# Power_Supply_Page_for_RK3399.net
KiCad netlist of a schematic drawn in Altium Designer
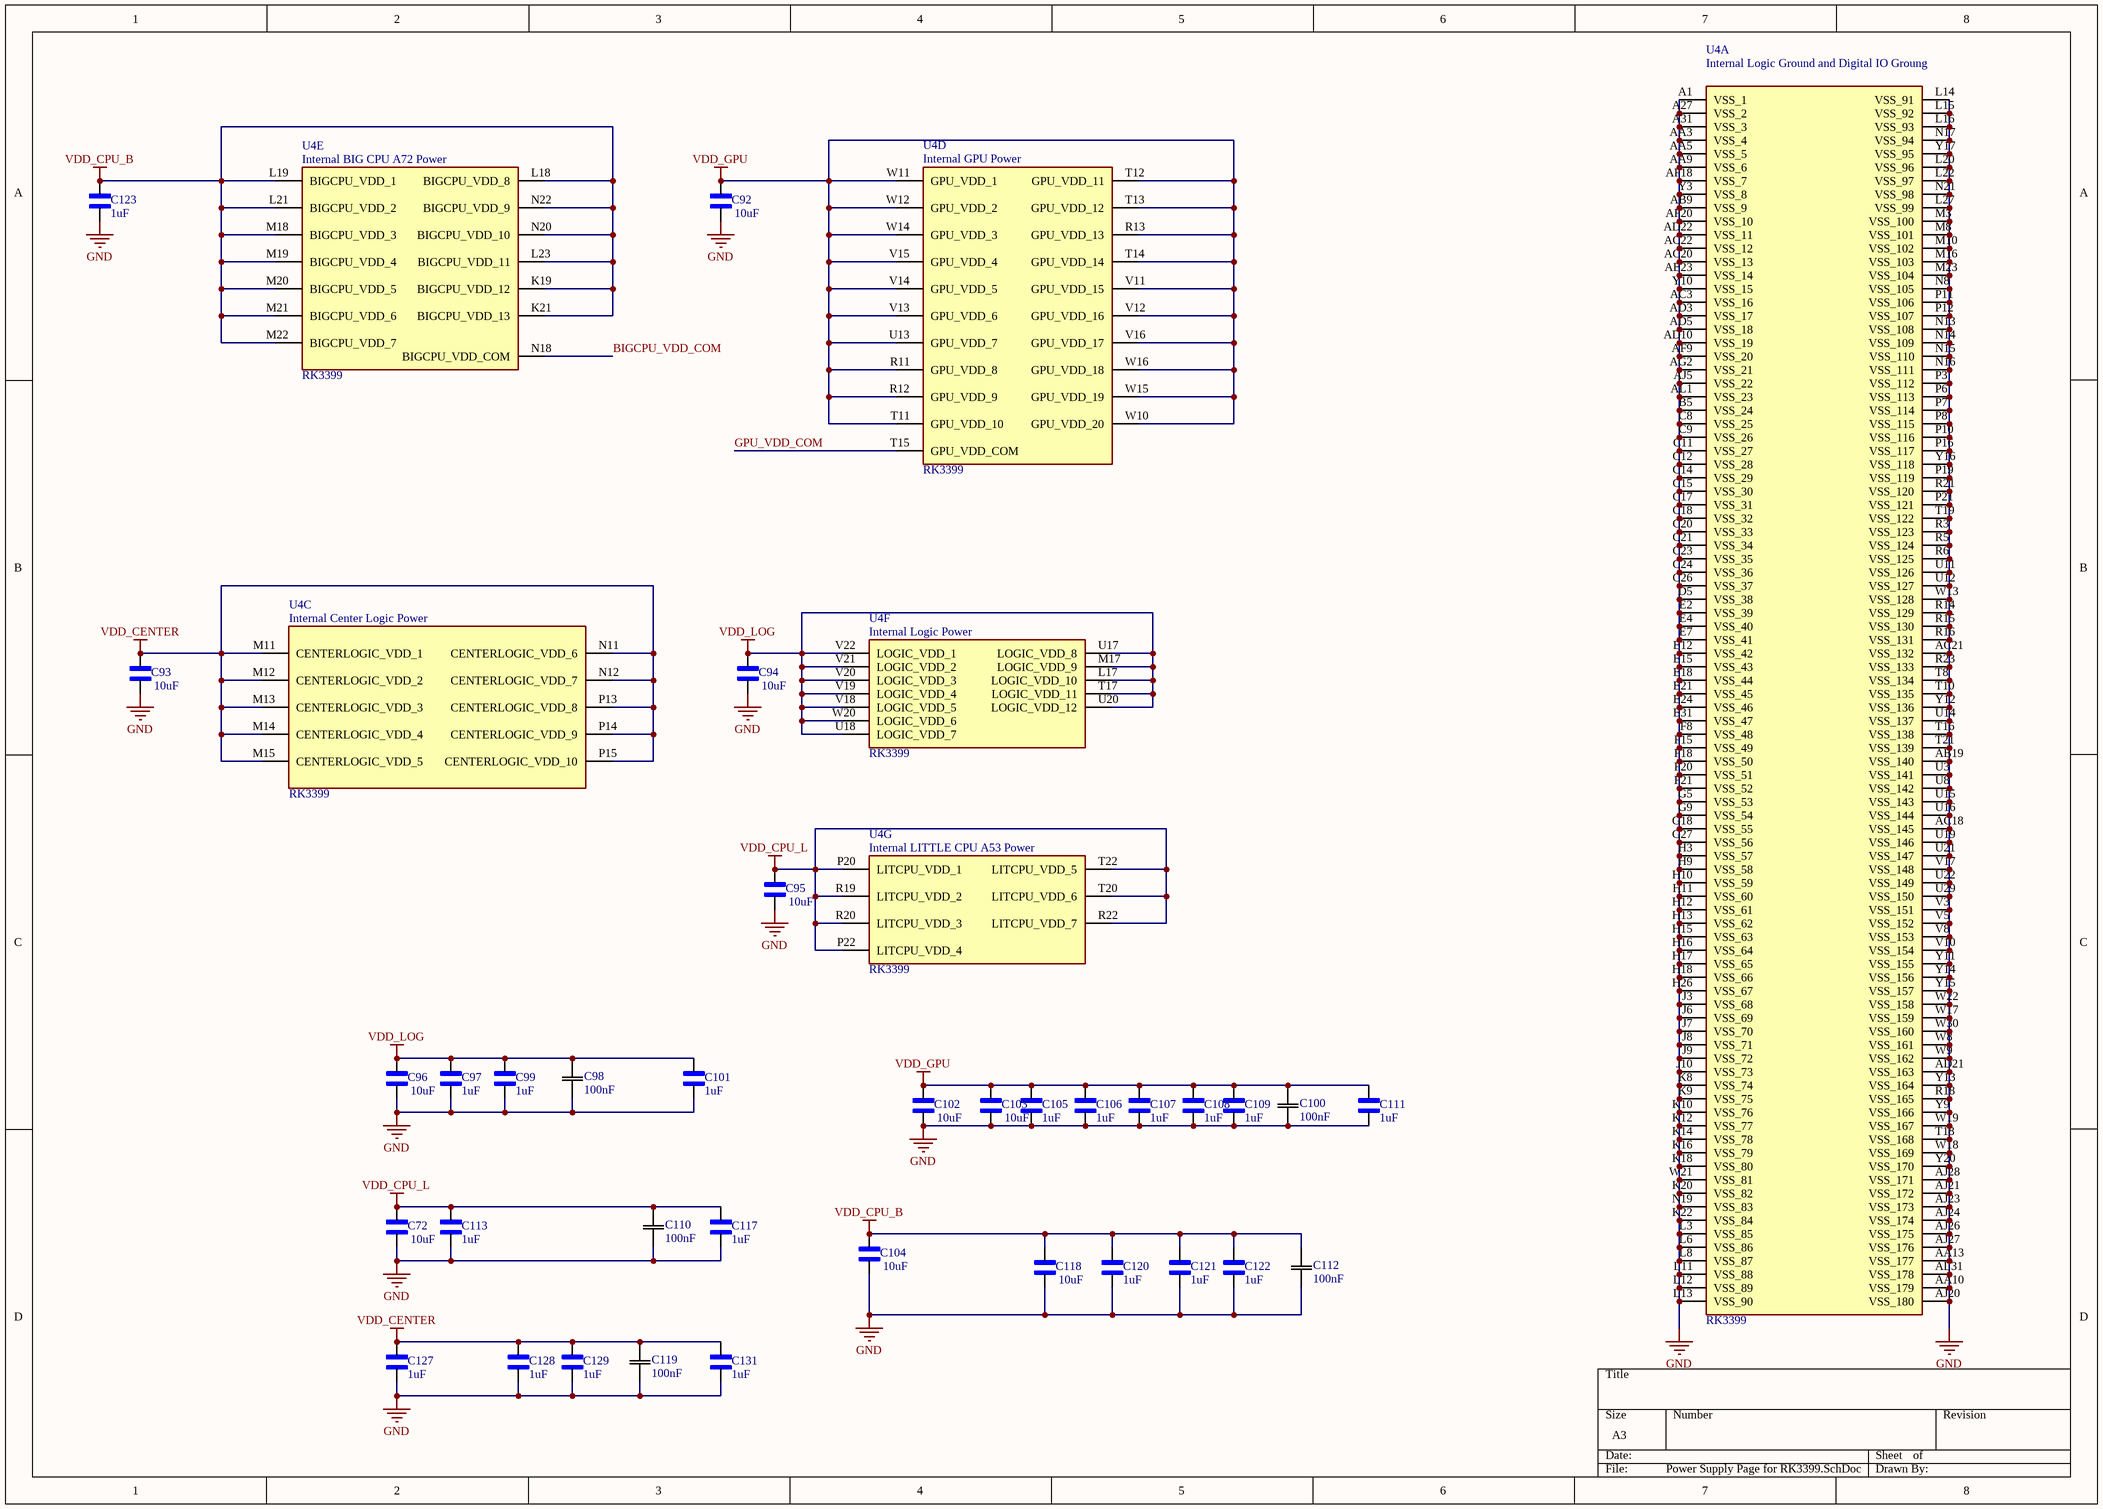
[diagram p0: Power Supply Page for RK3399.SchDoc]

(export (version "E")
  (design (tool "Eeschema 10.0.6"))
  (components
    (comp (ref "C72")
      (value "10uF")
      (footprint "CAPC1005X70N")
      (description "10 ÂµF Â±20% 6.3V Ceramic Capacitor X5R 0402 (1005 Metric)")
      (fields (field (name "MF") "Samsung") (field (name "MP") "CL05A106MQ5NUNC"))
      (libsource (lib "CL05A106MQ5NUNC") (part "CL05A106MQ5NUNC"))
    )
    (comp (ref "C92")
      (value "10uF")
      (footprint "CAPC1005X70N")
      (description "10 ÂµF Â±20% 6.3V Ceramic Capacitor X5R 0402 (1005 Metric)")
      (fields (field (name "MF") "Samsung") (field (name "MP") "CL05A106MQ5NUNC"))
      (libsource (lib "CL05A106MQ5NUNC") (part "CL05A106MQ5NUNC"))
    )
    (comp (ref "C93")
      (value "10uF")
      (footprint "CAPC1005X70N")
      (description "10 ÂµF Â±20% 6.3V Ceramic Capacitor X5R 0402 (1005 Metric)")
      (fields (field (name "MF") "Samsung") (field (name "MP") "CL05A106MQ5NUNC"))
      (libsource (lib "CL05A106MQ5NUNC") (part "CL05A106MQ5NUNC"))
    )
    (comp (ref "C94")
      (value "10uF")
      (footprint "CAPC1005X70N")
      (description "10 ÂµF Â±20% 6.3V Ceramic Capacitor X5R 0402 (1005 Metric)")
      (fields (field (name "MF") "Samsung") (field (name "MP") "CL05A106MQ5NUNC"))
      (libsource (lib "CL05A106MQ5NUNC") (part "CL05A106MQ5NUNC"))
    )
    (comp (ref "C95")
      (value "10uF")
      (footprint "CAPC1005X70N")
      (description "10 ÂµF Â±20% 6.3V Ceramic Capacitor X5R 0402 (1005 Metric)")
      (fields (field (name "MF") "Samsung") (field (name "MP") "CL05A106MQ5NUNC"))
      (libsource (lib "CL05A106MQ5NUNC") (part "CL05A106MQ5NUNC"))
    )
    (comp (ref "C96")
      (value "10uF")
      (footprint "CAPC1005X70N")
      (description "10 ÂµF Â±20% 6.3V Ceramic Capacitor X5R 0402 (1005 Metric)")
      (fields (field (name "MF") "Samsung") (field (name "MP") "CL05A106MQ5NUNC"))
      (libsource (lib "CL05A106MQ5NUNC") (part "CL05A106MQ5NUNC"))
    )
    (comp (ref "C97")
      (value "1uF")
      (footprint "CAPC1005X56N")
      (description "1 ÂµF Â±10% 10V Ceramic Capacitor X5R 0402 (1005 Metric)")
      (fields (field (name "MF") "AVX") (field (name "MP") "0402ZD105KAT4A"))
      (libsource (lib "0402ZD105KAT4A") (part "0402ZD105KAT4A"))
    )
    (comp (ref "C98")
      (value "100nF")
      (footprint "CAP_1005_TDK")
      (description "Description")
      (fields
        (field (name "MANUFACTURER_PART_NUMBER") "C1005X7R1H104M050BB")
        (field (name "COPYRIGHT") "Copyright (C) 2025 Ultra Librarian. All rights reserved.")
      )
      (libsource (lib "C1005X7R1H104M050BB") (part "C1005X7R1H104M050BB"))
    )
    (comp (ref "C99")
      (value "1uF")
      (footprint "CAPC1005X56N")
      (description "1 ÂµF Â±10% 10V Ceramic Capacitor X5R 0402 (1005 Metric)")
      (fields (field (name "MF") "AVX") (field (name "MP") "0402ZD105KAT4A"))
      (libsource (lib "0402ZD105KAT4A") (part "0402ZD105KAT4A"))
    )
    (comp (ref "C100")
      (value "100nF")
      (footprint "CAP_1005_TDK")
      (description "Description")
      (fields
        (field (name "MANUFACTURER_PART_NUMBER") "C1005X7R1H104M050BB")
        (field (name "COPYRIGHT") "Copyright (C) 2025 Ultra Librarian. All rights reserved.")
      )
      (libsource (lib "C1005X7R1H104M050BB") (part "C1005X7R1H104M050BB"))
    )
    (comp (ref "C101")
      (value "1uF")
      (footprint "CAPC1005X56N")
      (description "1 ÂµF Â±10% 10V Ceramic Capacitor X5R 0402 (1005 Metric)")
      (fields (field (name "MF") "AVX") (field (name "MP") "0402ZD105KAT4A"))
      (libsource (lib "0402ZD105KAT4A") (part "0402ZD105KAT4A"))
    )
    (comp (ref "C102")
      (value "10uF")
      (footprint "CAPC1005X70N")
      (description "10 ÂµF Â±20% 6.3V Ceramic Capacitor X5R 0402 (1005 Metric)")
      (fields (field (name "MF") "Samsung") (field (name "MP") "CL05A106MQ5NUNC"))
      (libsource (lib "CL05A106MQ5NUNC") (part "CL05A106MQ5NUNC"))
    )
    (comp (ref "C103")
      (value "10uF")
      (footprint "CAPC1005X70N")
      (description "10 ÂµF Â±20% 6.3V Ceramic Capacitor X5R 0402 (1005 Metric)")
      (fields (field (name "MF") "Samsung") (field (name "MP") "CL05A106MQ5NUNC"))
      (libsource (lib "CL05A106MQ5NUNC") (part "CL05A106MQ5NUNC"))
    )
    (comp (ref "C104")
      (value "10uF")
      (footprint "CAPC1005X70N")
      (description "10 ÂµF Â±20% 6.3V Ceramic Capacitor X5R 0402 (1005 Metric)")
      (fields (field (name "MF") "Samsung") (field (name "MP") "CL05A106MQ5NUNC"))
      (libsource (lib "CL05A106MQ5NUNC") (part "CL05A106MQ5NUNC"))
    )
    (comp (ref "C105")
      (value "1uF")
      (footprint "CAPC1005X56N")
      (description "1 ÂµF Â±10% 10V Ceramic Capacitor X5R 0402 (1005 Metric)")
      (fields (field (name "MF") "AVX") (field (name "MP") "0402ZD105KAT4A"))
      (libsource (lib "0402ZD105KAT4A") (part "0402ZD105KAT4A"))
    )
    (comp (ref "C106")
      (value "1uF")
      (footprint "CAPC1005X56N")
      (description "1 ÂµF Â±10% 10V Ceramic Capacitor X5R 0402 (1005 Metric)")
      (fields (field (name "MF") "AVX") (field (name "MP") "0402ZD105KAT4A"))
      (libsource (lib "0402ZD105KAT4A") (part "0402ZD105KAT4A"))
    )
    (comp (ref "C107")
      (value "1uF")
      (footprint "CAPC1005X56N")
      (description "1 ÂµF Â±10% 10V Ceramic Capacitor X5R 0402 (1005 Metric)")
      (fields (field (name "MF") "AVX") (field (name "MP") "0402ZD105KAT4A"))
      (libsource (lib "0402ZD105KAT4A") (part "0402ZD105KAT4A"))
    )
    (comp (ref "C108")
      (value "1uF")
      (footprint "CAPC1005X56N")
      (description "1 ÂµF Â±10% 10V Ceramic Capacitor X5R 0402 (1005 Metric)")
      (fields (field (name "MF") "AVX") (field (name "MP") "0402ZD105KAT4A"))
      (libsource (lib "0402ZD105KAT4A") (part "0402ZD105KAT4A"))
    )
    (comp (ref "C109")
      (value "1uF")
      (footprint "CAPC1005X56N")
      (description "1 ÂµF Â±10% 10V Ceramic Capacitor X5R 0402 (1005 Metric)")
      (fields (field (name "MF") "AVX") (field (name "MP") "0402ZD105KAT4A"))
      (libsource (lib "0402ZD105KAT4A") (part "0402ZD105KAT4A"))
    )
    (comp (ref "C110")
      (value "100nF")
      (footprint "CAP_1005_TDK")
      (description "Description")
      (fields
        (field (name "MANUFACTURER_PART_NUMBER") "C1005X7R1H104M050BB")
        (field (name "COPYRIGHT") "Copyright (C) 2025 Ultra Librarian. All rights reserved.")
      )
      (libsource (lib "C1005X7R1H104M050BB") (part "C1005X7R1H104M050BB"))
    )
    (comp (ref "C111")
      (value "1uF")
      (footprint "CAPC1005X56N")
      (description "1 ÂµF Â±10% 10V Ceramic Capacitor X5R 0402 (1005 Metric)")
      (fields (field (name "MF") "AVX") (field (name "MP") "0402ZD105KAT4A"))
      (libsource (lib "0402ZD105KAT4A") (part "0402ZD105KAT4A"))
    )
    (comp (ref "C112")
      (value "100nF")
      (footprint "CAP_1005_TDK")
      (description "Description")
      (fields
        (field (name "MANUFACTURER_PART_NUMBER") "C1005X7R1H104M050BB")
        (field (name "COPYRIGHT") "Copyright (C) 2025 Ultra Librarian. All rights reserved.")
      )
      (libsource (lib "C1005X7R1H104M050BB") (part "C1005X7R1H104M050BB"))
    )
    (comp (ref "C113")
      (value "1uF")
      (footprint "CAPC1005X56N")
      (description "1 ÂµF Â±10% 10V Ceramic Capacitor X5R 0402 (1005 Metric)")
      (fields (field (name "MF") "AVX") (field (name "MP") "0402ZD105KAT4A"))
      (libsource (lib "0402ZD105KAT4A") (part "0402ZD105KAT4A"))
    )
    (comp (ref "C117")
      (value "1uF")
      (footprint "CAPC1005X56N")
      (description "1 ÂµF Â±10% 10V Ceramic Capacitor X5R 0402 (1005 Metric)")
      (fields (field (name "MF") "AVX") (field (name "MP") "0402ZD105KAT4A"))
      (libsource (lib "0402ZD105KAT4A") (part "0402ZD105KAT4A"))
    )
    (comp (ref "C118")
      (value "10uF")
      (footprint "CAPC1005X70N")
      (description "10 ÂµF Â±20% 6.3V Ceramic Capacitor X5R 0402 (1005 Metric)")
      (fields (field (name "MF") "Samsung") (field (name "MP") "CL05A106MQ5NUNC"))
      (libsource (lib "CL05A106MQ5NUNC") (part "CL05A106MQ5NUNC"))
    )
    (comp (ref "C119")
      (value "100nF")
      (footprint "CAP_1005_TDK")
      (description "Description")
      (fields
        (field (name "MANUFACTURER_PART_NUMBER") "C1005X7R1H104M050BB")
        (field (name "COPYRIGHT") "Copyright (C) 2025 Ultra Librarian. All rights reserved.")
      )
      (libsource (lib "C1005X7R1H104M050BB") (part "C1005X7R1H104M050BB"))
    )
    (comp (ref "C120")
      (value "1uF")
      (footprint "CAPC1005X56N")
      (description "1 ÂµF Â±10% 10V Ceramic Capacitor X5R 0402 (1005 Metric)")
      (fields (field (name "MF") "AVX") (field (name "MP") "0402ZD105KAT4A"))
      (libsource (lib "0402ZD105KAT4A") (part "0402ZD105KAT4A"))
    )
    (comp (ref "C121")
      (value "1uF")
      (footprint "CAPC1005X56N")
      (description "1 ÂµF Â±10% 10V Ceramic Capacitor X5R 0402 (1005 Metric)")
      (fields (field (name "MF") "AVX") (field (name "MP") "0402ZD105KAT4A"))
      (libsource (lib "0402ZD105KAT4A") (part "0402ZD105KAT4A"))
    )
    (comp (ref "C122")
      (value "1uF")
      (footprint "CAPC1005X56N")
      (description "1 ÂµF Â±10% 10V Ceramic Capacitor X5R 0402 (1005 Metric)")
      (fields (field (name "MF") "AVX") (field (name "MP") "0402ZD105KAT4A"))
      (libsource (lib "0402ZD105KAT4A") (part "0402ZD105KAT4A"))
    )
    (comp (ref "C123")
      (value "1uF")
      (footprint "CAPC1005X56N")
      (description "1 ÂµF Â±10% 10V Ceramic Capacitor X5R 0402 (1005 Metric)")
      (fields (field (name "MF") "AVX") (field (name "MP") "0402ZD105KAT4A"))
      (libsource (lib "0402ZD105KAT4A") (part "0402ZD105KAT4A"))
    )
    (comp (ref "C127")
      (value "1uF")
      (footprint "CAPC1005X56N")
      (description "1 ÂµF Â±10% 10V Ceramic Capacitor X5R 0402 (1005 Metric)")
      (fields (field (name "MF") "AVX") (field (name "MP") "0402ZD105KAT4A"))
      (libsource (lib "0402ZD105KAT4A") (part "0402ZD105KAT4A"))
    )
    (comp (ref "C128")
      (value "1uF")
      (footprint "CAPC1005X56N")
      (description "1 ÂµF Â±10% 10V Ceramic Capacitor X5R 0402 (1005 Metric)")
      (fields (field (name "MF") "AVX") (field (name "MP") "0402ZD105KAT4A"))
      (libsource (lib "0402ZD105KAT4A") (part "0402ZD105KAT4A"))
    )
    (comp (ref "C129")
      (value "1uF")
      (footprint "CAPC1005X56N")
      (description "1 ÂµF Â±10% 10V Ceramic Capacitor X5R 0402 (1005 Metric)")
      (fields (field (name "MF") "AVX") (field (name "MP") "0402ZD105KAT4A"))
      (libsource (lib "0402ZD105KAT4A") (part "0402ZD105KAT4A"))
    )
    (comp (ref "C131")
      (value "1uF")
      (footprint "CAPC1005X56N")
      (description "1 ÂµF Â±10% 10V Ceramic Capacitor X5R 0402 (1005 Metric)")
      (fields (field (name "MF") "AVX") (field (name "MP") "0402ZD105KAT4A"))
      (libsource (lib "0402ZD105KAT4A") (part "0402ZD105KAT4A"))
    )
    (comp (ref "U4")
      (value "RK3399")
      (footprint "BGA828C65P31X31_2100X2100X161N")
      (description "RK3399 ROCK Pi 4 Model A 2GB - ARMÂ® CortexÂ®-A53, CortexÂ®-A72 MPU Embedded Evaluation Board")
      (fields (field (name "MF") "Rockchip"))
      (libsource (lib "RK3399") (part "RK3399"))
    )
  )
  (nets
    (net (code "1") (name "/BIGCPU_VDD_COM") (class "Default")
      (node (ref "U4") (pin "N18") (pinfunction "BIGCPU_VDD_COM_N18") (pintype "power_in"))
    )
    (net (code "2") (name "/GPU_VDD_COM") (class "Default")
      (node (ref "U4") (pin "T15") (pinfunction "GPU_VDD_COM_T15") (pintype "power_in"))
    )
    (net (code "3") (name "GND") (class "Default")
      (node (ref "C100") (pin "1") (pinfunction "1_1") (pintype "passive"))
      (node (ref "C101") (pin "1") (pinfunction "1_1") (pintype "passive"))
      (node (ref "C102") (pin "1") (pinfunction "1_1") (pintype "passive"))
      (node (ref "C103") (pin "1") (pinfunction "1_1") (pintype "passive"))
      (node (ref "C104") (pin "1") (pinfunction "1_1") (pintype "passive"))
      (node (ref "C105") (pin "1") (pinfunction "1_1") (pintype "passive"))
      (node (ref "C106") (pin "1") (pinfunction "1_1") (pintype "passive"))
      (node (ref "C107") (pin "1") (pinfunction "1_1") (pintype "passive"))
      (node (ref "C108") (pin "1") (pinfunction "1_1") (pintype "passive"))
      (node (ref "C109") (pin "1") (pinfunction "1_1") (pintype "passive"))
      (node (ref "C110") (pin "1") (pinfunction "1_1") (pintype "passive"))
      (node (ref "C111") (pin "1") (pinfunction "1_1") (pintype "passive"))
      (node (ref "C112") (pin "1") (pinfunction "1_1") (pintype "passive"))
      (node (ref "C113") (pin "1") (pinfunction "1_1") (pintype "passive"))
      (node (ref "C117") (pin "1") (pinfunction "1_1") (pintype "passive"))
      (node (ref "C118") (pin "1") (pinfunction "1_1") (pintype "passive"))
      (node (ref "C119") (pin "1") (pinfunction "1_1") (pintype "passive"))
      (node (ref "C120") (pin "1") (pinfunction "1_1") (pintype "passive"))
      (node (ref "C121") (pin "1") (pinfunction "1_1") (pintype "passive"))
      (node (ref "C122") (pin "1") (pinfunction "1_1") (pintype "passive"))
      (node (ref "C123") (pin "1") (pinfunction "1_1") (pintype "passive"))
      (node (ref "C127") (pin "1") (pinfunction "1_1") (pintype "passive"))
      (node (ref "C128") (pin "1") (pinfunction "1_1") (pintype "passive"))
      (node (ref "C129") (pin "1") (pinfunction "1_1") (pintype "passive"))
      (node (ref "C131") (pin "1") (pinfunction "1_1") (pintype "passive"))
      (node (ref "C72") (pin "1") (pinfunction "1_1") (pintype "passive"))
      (node (ref "C92") (pin "1") (pinfunction "1_1") (pintype "passive"))
      (node (ref "C93") (pin "1") (pinfunction "1_1") (pintype "passive"))
      (node (ref "C94") (pin "1") (pinfunction "1_1") (pintype "passive"))
      (node (ref "C95") (pin "1") (pinfunction "1_1") (pintype "passive"))
      (node (ref "C96") (pin "1") (pinfunction "1_1") (pintype "passive"))
      (node (ref "C97") (pin "1") (pinfunction "1_1") (pintype "passive"))
      (node (ref "C98") (pin "1") (pinfunction "1_1") (pintype "passive"))
      (node (ref "C99") (pin "1") (pinfunction "1_1") (pintype "passive"))
      (node (ref "U4") (pin "A1") (pinfunction "VSS_1_A1") (pintype "power_in"))
      (node (ref "U4") (pin "A27") (pinfunction "VSS_2_A27") (pintype "power_in"))
      (node (ref "U4") (pin "A31") (pinfunction "VSS_3_A31") (pintype "power_in"))
      (node (ref "U4") (pin "AA10") (pinfunction "VSS_179_AA10") (pintype "power_in"))
      (node (ref "U4") (pin "AA13") (pinfunction "VSS_177_AA13") (pintype "power_in"))
      (node (ref "U4") (pin "AA3") (pinfunction "VSS_4_AA3") (pintype "power_in"))
      (node (ref "U4") (pin "AA5") (pinfunction "VSS_5_AA5") (pintype "power_in"))
      (node (ref "U4") (pin "AA9") (pinfunction "VSS_6_AA9") (pintype "power_in"))
      (node (ref "U4") (pin "AB19") (pinfunction "VSS_140_AB19") (pintype "power_in"))
      (node (ref "U4") (pin "AB9") (pinfunction "VSS_9_AB9") (pintype "power_in"))
      (node (ref "U4") (pin "AC18") (pinfunction "VSS_145_AC18") (pintype "power_in"))
      (node (ref "U4") (pin "AC20") (pinfunction "VSS_13_AC20") (pintype "power_in"))
      (node (ref "U4") (pin "AC21") (pinfunction "VSS_132_AC21") (pintype "power_in"))
      (node (ref "U4") (pin "AC22") (pinfunction "VSS_12_AC22") (pintype "power_in"))
      (node (ref "U4") (pin "AC3") (pinfunction "VSS_16_AC3") (pintype "power_in"))
      (node (ref "U4") (pin "AD10") (pinfunction "VSS_19_AD10") (pintype "power_in"))
      (node (ref "U4") (pin "AD21") (pinfunction "VSS_163_AD21") (pintype "power_in"))
      (node (ref "U4") (pin "AD22") (pinfunction "VSS_11_AD22") (pintype "power_in"))
      (node (ref "U4") (pin "AD3") (pinfunction "VSS_17_AD3") (pintype "power_in"))
      (node (ref "U4") (pin "AD5") (pinfunction "VSS_18_AD5") (pintype "power_in"))
      (node (ref "U4") (pin "AE23") (pinfunction "VSS_14_AE23") (pintype "power_in"))
      (node (ref "U4") (pin "AF18") (pinfunction "VSS_7_AF18") (pintype "power_in"))
      (node (ref "U4") (pin "AF20") (pinfunction "VSS_10_AF20") (pintype "power_in"))
      (node (ref "U4") (pin "AF9") (pinfunction "VSS_20_AF9") (pintype "power_in"))
      (node (ref "U4") (pin "AG2") (pinfunction "VSS_21_AG2") (pintype "power_in"))
      (node (ref "U4") (pin "AJ20") (pinfunction "VSS_180_AJ20") (pintype "power_in"))
      (node (ref "U4") (pin "AJ21") (pinfunction "VSS_172_AJ21") (pintype "power_in"))
      (node (ref "U4") (pin "AJ23") (pinfunction "VSS_173_AJ23") (pintype "power_in"))
      (node (ref "U4") (pin "AJ24") (pinfunction "VSS_174_AJ24") (pintype "power_in"))
      (node (ref "U4") (pin "AJ26") (pinfunction "VSS_175_AJ26") (pintype "power_in"))
      (node (ref "U4") (pin "AJ27") (pinfunction "VSS_176_AJ27") (pintype "power_in"))
      (node (ref "U4") (pin "AJ28") (pinfunction "VSS_171_AJ28") (pintype "power_in"))
      (node (ref "U4") (pin "AJ5") (pinfunction "VSS_22_AJ5") (pintype "power_in"))
      (node (ref "U4") (pin "AL1") (pinfunction "VSS_23_AL1") (pintype "power_in"))
      (node (ref "U4") (pin "AL31") (pinfunction "VSS_178_AL31") (pintype "power_in"))
      (node (ref "U4") (pin "B5") (pinfunction "VSS_24_B5") (pintype "power_in"))
      (node (ref "U4") (pin "C11") (pinfunction "VSS_27_C11") (pintype "power_in"))
      (node (ref "U4") (pin "C12") (pinfunction "VSS_28_C12") (pintype "power_in"))
      (node (ref "U4") (pin "C14") (pinfunction "VSS_29_C14") (pintype "power_in"))
      (node (ref "U4") (pin "C15") (pinfunction "VSS_30_C15") (pintype "power_in"))
      (node (ref "U4") (pin "C17") (pinfunction "VSS_31_C17") (pintype "power_in"))
      (node (ref "U4") (pin "C18") (pinfunction "VSS_32_C18") (pintype "power_in"))
      (node (ref "U4") (pin "C20") (pinfunction "VSS_33_C20") (pintype "power_in"))
      (node (ref "U4") (pin "C21") (pinfunction "VSS_34_C21") (pintype "power_in"))
      (node (ref "U4") (pin "C23") (pinfunction "VSS_35_C23") (pintype "power_in"))
      (node (ref "U4") (pin "C24") (pinfunction "VSS_36_C24") (pintype "power_in"))
      (node (ref "U4") (pin "C26") (pinfunction "VSS_37_C26") (pintype "power_in"))
      (node (ref "U4") (pin "C8") (pinfunction "VSS_25_C8") (pintype "power_in"))
      (node (ref "U4") (pin "C9") (pinfunction "VSS_26_C9") (pintype "power_in"))
      (node (ref "U4") (pin "D5") (pinfunction "VSS_38_D5") (pintype "power_in"))
      (node (ref "U4") (pin "E12") (pinfunction "VSS_42_E12") (pintype "power_in"))
      (node (ref "U4") (pin "E15") (pinfunction "VSS_43_E15") (pintype "power_in"))
      (node (ref "U4") (pin "E18") (pinfunction "VSS_44_E18") (pintype "power_in"))
      (node (ref "U4") (pin "E2") (pinfunction "VSS_39_E2") (pintype "power_in"))
      (node (ref "U4") (pin "E21") (pinfunction "VSS_45_E21") (pintype "power_in"))
      (node (ref "U4") (pin "E24") (pinfunction "VSS_46_E24") (pintype "power_in"))
      (node (ref "U4") (pin "E31") (pinfunction "VSS_47_E31") (pintype "power_in"))
      (node (ref "U4") (pin "E4") (pinfunction "VSS_40_E4") (pintype "power_in"))
      (node (ref "U4") (pin "E7") (pinfunction "VSS_41_E7") (pintype "power_in"))
      (node (ref "U4") (pin "F15") (pinfunction "VSS_49_F15") (pintype "power_in"))
      (node (ref "U4") (pin "F18") (pinfunction "VSS_50_F18") (pintype "power_in"))
      (node (ref "U4") (pin "F20") (pinfunction "VSS_51_F20") (pintype "power_in"))
      (node (ref "U4") (pin "F21") (pinfunction "VSS_52_F21") (pintype "power_in"))
      (node (ref "U4") (pin "F8") (pinfunction "VSS_48_F8") (pintype "power_in"))
      (node (ref "U4") (pin "G18") (pinfunction "VSS_55_G18") (pintype "power_in"))
      (node (ref "U4") (pin "G27") (pinfunction "VSS_56_G27") (pintype "power_in"))
      (node (ref "U4") (pin "G5") (pinfunction "VSS_53_G5") (pintype "power_in"))
      (node (ref "U4") (pin "G9") (pinfunction "VSS_54_G9") (pintype "power_in"))
      (node (ref "U4") (pin "H10") (pinfunction "VSS_59_H10") (pintype "power_in"))
      (node (ref "U4") (pin "H11") (pinfunction "VSS_60_H11") (pintype "power_in"))
      (node (ref "U4") (pin "H12") (pinfunction "VSS_61_H12") (pintype "power_in"))
      (node (ref "U4") (pin "H13") (pinfunction "VSS_62_H13") (pintype "power_in"))
      (node (ref "U4") (pin "H15") (pinfunction "VSS_63_H15") (pintype "power_in"))
      (node (ref "U4") (pin "H16") (pinfunction "VSS_64_H16") (pintype "power_in"))
      (node (ref "U4") (pin "H17") (pinfunction "VSS_65_H17") (pintype "power_in"))
      (node (ref "U4") (pin "H18") (pinfunction "VSS_66_H18") (pintype "power_in"))
      (node (ref "U4") (pin "H26") (pinfunction "VSS_67_H26") (pintype "power_in"))
      (node (ref "U4") (pin "H3") (pinfunction "VSS_57_H3") (pintype "power_in"))
      (node (ref "U4") (pin "H9") (pinfunction "VSS_58_H9") (pintype "power_in"))
      (node (ref "U4") (pin "J10") (pinfunction "VSS_73_J10") (pintype "power_in"))
      (node (ref "U4") (pin "J3") (pinfunction "VSS_68_J3") (pintype "power_in"))
      (node (ref "U4") (pin "J6") (pinfunction "VSS_69_J6") (pintype "power_in"))
      (node (ref "U4") (pin "J7") (pinfunction "VSS_70_J7") (pintype "power_in"))
      (node (ref "U4") (pin "J8") (pinfunction "VSS_71_J8") (pintype "power_in"))
      (node (ref "U4") (pin "J9") (pinfunction "VSS_72_J9") (pintype "power_in"))
      (node (ref "U4") (pin "K10") (pinfunction "VSS_76_K10") (pintype "power_in"))
      (node (ref "U4") (pin "K12") (pinfunction "VSS_77_K12") (pintype "power_in"))
      (node (ref "U4") (pin "K14") (pinfunction "VSS_78_K14") (pintype "power_in"))
      (node (ref "U4") (pin "K16") (pinfunction "VSS_79_K16") (pintype "power_in"))
      (node (ref "U4") (pin "K18") (pinfunction "VSS_80_K18") (pintype "power_in"))
      (node (ref "U4") (pin "K20") (pinfunction "VSS_82_K20") (pintype "power_in"))
      (node (ref "U4") (pin "K22") (pinfunction "VSS_84_K22") (pintype "power_in"))
      (node (ref "U4") (pin "K8") (pinfunction "VSS_74_K8") (pintype "power_in"))
      (node (ref "U4") (pin "K9") (pinfunction "VSS_75_K9") (pintype "power_in"))
      (node (ref "U4") (pin "L11") (pinfunction "VSS_88_L11") (pintype "power_in"))
      (node (ref "U4") (pin "L12") (pinfunction "VSS_89_L12") (pintype "power_in"))
      (node (ref "U4") (pin "L13") (pinfunction "VSS_90_L13") (pintype "power_in"))
      (node (ref "U4") (pin "L14") (pinfunction "VSS_91_L14") (pintype "power_in"))
      (node (ref "U4") (pin "L15") (pinfunction "VSS_92_L15") (pintype "power_in"))
      (node (ref "U4") (pin "L16") (pinfunction "VSS_93_L16") (pintype "power_in"))
      (node (ref "U4") (pin "L20") (pinfunction "VSS_96_L20") (pintype "power_in"))
      (node (ref "U4") (pin "L22") (pinfunction "VSS_97_L22") (pintype "power_in"))
      (node (ref "U4") (pin "L27") (pinfunction "VSS_99_L27") (pintype "power_in"))
      (node (ref "U4") (pin "L3") (pinfunction "VSS_85_L3") (pintype "power_in"))
      (node (ref "U4") (pin "L6") (pinfunction "VSS_86_L6") (pintype "power_in"))
      (node (ref "U4") (pin "L8") (pinfunction "VSS_87_L8") (pintype "power_in"))
      (node (ref "U4") (pin "M10") (pinfunction "VSS_102_M10") (pintype "power_in"))
      (node (ref "U4") (pin "M16") (pinfunction "VSS_103_M16") (pintype "power_in"))
      (node (ref "U4") (pin "M23") (pinfunction "VSS_104_M23") (pintype "power_in"))
      (node (ref "U4") (pin "M3") (pinfunction "VSS_100_M3") (pintype "power_in"))
      (node (ref "U4") (pin "M8") (pinfunction "VSS_101_M8") (pintype "power_in"))
      (node (ref "U4") (pin "N13") (pinfunction "VSS_108_N13") (pintype "power_in"))
      (node (ref "U4") (pin "N14") (pinfunction "VSS_109_N14") (pintype "power_in"))
      (node (ref "U4") (pin "N15") (pinfunction "VSS_110_N15") (pintype "power_in"))
      (node (ref "U4") (pin "N16") (pinfunction "VSS_111_N16") (pintype "power_in"))
      (node (ref "U4") (pin "N17") (pinfunction "VSS_94_N17") (pintype "power_in"))
      (node (ref "U4") (pin "N19") (pinfunction "VSS_83_N19") (pintype "power_in"))
      (node (ref "U4") (pin "N21") (pinfunction "VSS_98_N21") (pintype "power_in"))
      (node (ref "U4") (pin "N8") (pinfunction "VSS_105_N8") (pintype "power_in"))
      (node (ref "U4") (pin "P10") (pinfunction "VSS_116_P10") (pintype "power_in"))
      (node (ref "U4") (pin "P11") (pinfunction "VSS_106_P11") (pintype "power_in"))
      (node (ref "U4") (pin "P12") (pinfunction "VSS_107_P12") (pintype "power_in"))
      (node (ref "U4") (pin "P16") (pinfunction "VSS_117_P16") (pintype "power_in"))
      (node (ref "U4") (pin "P19") (pinfunction "VSS_119_P19") (pintype "power_in"))
      (node (ref "U4") (pin "P21") (pinfunction "VSS_121_P21") (pintype "power_in"))
      (node (ref "U4") (pin "P3") (pinfunction "VSS_112_P3") (pintype "power_in"))
      (node (ref "U4") (pin "P6") (pinfunction "VSS_113_P6") (pintype "power_in"))
      (node (ref "U4") (pin "P7") (pinfunction "VSS_114_P7") (pintype "power_in"))
      (node (ref "U4") (pin "P8") (pinfunction "VSS_115_P8") (pintype "power_in"))
      (node (ref "U4") (pin "R14") (pinfunction "VSS_129_R14") (pintype "power_in"))
      (node (ref "U4") (pin "R15") (pinfunction "VSS_130_R15") (pintype "power_in"))
      (node (ref "U4") (pin "R16") (pinfunction "VSS_131_R16") (pintype "power_in"))
      (node (ref "U4") (pin "R18") (pinfunction "VSS_165_R18") (pintype "power_in"))
      (node (ref "U4") (pin "R21") (pinfunction "VSS_120_R21") (pintype "power_in"))
      (node (ref "U4") (pin "R23") (pinfunction "VSS_133_R23") (pintype "power_in"))
      (node (ref "U4") (pin "R3") (pinfunction "VSS_123_R3") (pintype "power_in"))
      (node (ref "U4") (pin "R5") (pinfunction "VSS_124_R5") (pintype "power_in"))
      (node (ref "U4") (pin "R6") (pinfunction "VSS_125_R6") (pintype "power_in"))
      (node (ref "U4") (pin "T10") (pinfunction "VSS_135_T10") (pintype "power_in"))
      (node (ref "U4") (pin "T16") (pinfunction "VSS_138_T16") (pintype "power_in"))
      (node (ref "U4") (pin "T18") (pinfunction "VSS_168_T18") (pintype "power_in"))
      (node (ref "U4") (pin "T19") (pinfunction "VSS_122_T19") (pintype "power_in"))
      (node (ref "U4") (pin "T21") (pinfunction "VSS_139_T21") (pintype "power_in"))
      (node (ref "U4") (pin "T8") (pinfunction "VSS_134_T8") (pintype "power_in"))
      (node (ref "U4") (pin "U11") (pinfunction "VSS_126_U11") (pintype "power_in"))
      (node (ref "U4") (pin "U12") (pinfunction "VSS_127_U12") (pintype "power_in"))
      (node (ref "U4") (pin "U14") (pinfunction "VSS_137_U14") (pintype "power_in"))
      (node (ref "U4") (pin "U15") (pinfunction "VSS_143_U15") (pintype "power_in"))
      (node (ref "U4") (pin "U16") (pinfunction "VSS_144_U16") (pintype "power_in"))
      (node (ref "U4") (pin "U19") (pinfunction "VSS_146_U19") (pintype "power_in"))
      (node (ref "U4") (pin "U21") (pinfunction "VSS_147_U21") (pintype "power_in"))
      (node (ref "U4") (pin "U22") (pinfunction "VSS_149_U22") (pintype "power_in"))
      (node (ref "U4") (pin "U29") (pinfunction "VSS_150_U29") (pintype "power_in"))
      (node (ref "U4") (pin "U3") (pinfunction "VSS_141_U3") (pintype "power_in"))
      (node (ref "U4") (pin "U8") (pinfunction "VSS_142_U8") (pintype "power_in"))
      (node (ref "U4") (pin "V10") (pinfunction "VSS_154_V10") (pintype "power_in"))
      (node (ref "U4") (pin "V17") (pinfunction "VSS_148_V17") (pintype "power_in"))
      (node (ref "U4") (pin "V3") (pinfunction "VSS_151_V3") (pintype "power_in"))
      (node (ref "U4") (pin "V5") (pinfunction "VSS_152_V5") (pintype "power_in"))
      (node (ref "U4") (pin "V8") (pinfunction "VSS_153_V8") (pintype "power_in"))
      (node (ref "U4") (pin "W13") (pinfunction "VSS_128_W13") (pintype "power_in"))
      (node (ref "U4") (pin "W17") (pinfunction "VSS_159_W17") (pintype "power_in"))
      (node (ref "U4") (pin "W18") (pinfunction "VSS_169_W18") (pintype "power_in"))
      (node (ref "U4") (pin "W19") (pinfunction "VSS_167_W19") (pintype "power_in"))
      (node (ref "U4") (pin "W21") (pinfunction "VSS_81_W21") (pintype "power_in"))
      (node (ref "U4") (pin "W22") (pinfunction "VSS_158_W22") (pintype "power_in"))
      (node (ref "U4") (pin "W30") (pinfunction "VSS_160_W30") (pintype "power_in"))
      (node (ref "U4") (pin "W8") (pinfunction "VSS_161_W8") (pintype "power_in"))
      (node (ref "U4") (pin "W9") (pinfunction "VSS_162_W9") (pintype "power_in"))
      (node (ref "U4") (pin "Y10") (pinfunction "VSS_15_Y10") (pintype "power_in"))
      (node (ref "U4") (pin "Y11") (pinfunction "VSS_155_Y11") (pintype "power_in"))
      (node (ref "U4") (pin "Y12") (pinfunction "VSS_136_Y12") (pintype "power_in"))
      (node (ref "U4") (pin "Y13") (pinfunction "VSS_164_Y13") (pintype "power_in"))
      (node (ref "U4") (pin "Y14") (pinfunction "VSS_156_Y14") (pintype "power_in"))
      (node (ref "U4") (pin "Y15") (pinfunction "VSS_157_Y15") (pintype "power_in"))
      (node (ref "U4") (pin "Y16") (pinfunction "VSS_118_Y16") (pintype "power_in"))
      (node (ref "U4") (pin "Y17") (pinfunction "VSS_95_Y17") (pintype "power_in"))
      (node (ref "U4") (pin "Y20") (pinfunction "VSS_170_Y20") (pintype "power_in"))
      (node (ref "U4") (pin "Y3") (pinfunction "VSS_8_Y3") (pintype "power_in"))
      (node (ref "U4") (pin "Y9") (pinfunction "VSS_166_Y9") (pintype "power_in"))
    )
    (net (code "4") (name "VDD_CENTER") (class "Default")
      (node (ref "C119") (pin "2") (pinfunction "2_2") (pintype "passive"))
      (node (ref "C127") (pin "2") (pinfunction "2_2") (pintype "passive"))
      (node (ref "C128") (pin "2") (pinfunction "2_2") (pintype "passive"))
      (node (ref "C129") (pin "2") (pinfunction "2_2") (pintype "passive"))
      (node (ref "C131") (pin "2") (pinfunction "2_2") (pintype "passive"))
      (node (ref "C93") (pin "2") (pinfunction "2_2") (pintype "passive"))
      (node (ref "U4") (pin "M11") (pinfunction "CENTERLOGIC_VDD_1_M11") (pintype "power_in"))
      (node (ref "U4") (pin "M12") (pinfunction "CENTERLOGIC_VDD_2_M12") (pintype "power_in"))
      (node (ref "U4") (pin "M13") (pinfunction "CENTERLOGIC_VDD_3_M13") (pintype "power_in"))
      (node (ref "U4") (pin "M14") (pinfunction "CENTERLOGIC_VDD_4_M14") (pintype "power_in"))
      (node (ref "U4") (pin "M15") (pinfunction "CENTERLOGIC_VDD_5_M15") (pintype "power_in"))
      (node (ref "U4") (pin "N11") (pinfunction "CENTERLOGIC_VDD_6_N11") (pintype "power_in"))
      (node (ref "U4") (pin "N12") (pinfunction "CENTERLOGIC_VDD_7_N12") (pintype "power_in"))
      (node (ref "U4") (pin "P13") (pinfunction "CENTERLOGIC_VDD_8_P13") (pintype "power_in"))
      (node (ref "U4") (pin "P14") (pinfunction "CENTERLOGIC_VDD_9_P14") (pintype "power_in"))
      (node (ref "U4") (pin "P15") (pinfunction "CENTERLOGIC_VDD_10_P15") (pintype "power_in"))
    )
    (net (code "5") (name "VDD_CPU_B") (class "Default")
      (node (ref "C104") (pin "2") (pinfunction "2_2") (pintype "passive"))
      (node (ref "C112") (pin "2") (pinfunction "2_2") (pintype "passive"))
      (node (ref "C118") (pin "2") (pinfunction "2_2") (pintype "passive"))
      (node (ref "C120") (pin "2") (pinfunction "2_2") (pintype "passive"))
      (node (ref "C121") (pin "2") (pinfunction "2_2") (pintype "passive"))
      (node (ref "C122") (pin "2") (pinfunction "2_2") (pintype "passive"))
      (node (ref "C123") (pin "2") (pinfunction "2_2") (pintype "passive"))
      (node (ref "U4") (pin "K19") (pinfunction "BIGCPU_VDD_12_K19") (pintype "power_in"))
      (node (ref "U4") (pin "K21") (pinfunction "BIGCPU_VDD_13_K21") (pintype "power_in"))
      (node (ref "U4") (pin "L18") (pinfunction "BIGCPU_VDD_8_L18") (pintype "power_in"))
      (node (ref "U4") (pin "L19") (pinfunction "BIGCPU_VDD_1_L19") (pintype "power_in"))
      (node (ref "U4") (pin "L21") (pinfunction "BIGCPU_VDD_2_L21") (pintype "power_in"))
      (node (ref "U4") (pin "L23") (pinfunction "BIGCPU_VDD_11_L23") (pintype "power_in"))
      (node (ref "U4") (pin "M18") (pinfunction "BIGCPU_VDD_3_M18") (pintype "power_in"))
      (node (ref "U4") (pin "M19") (pinfunction "BIGCPU_VDD_4_M19") (pintype "power_in"))
      (node (ref "U4") (pin "M20") (pinfunction "BIGCPU_VDD_5_M20") (pintype "power_in"))
      (node (ref "U4") (pin "M21") (pinfunction "BIGCPU_VDD_6_M21") (pintype "power_in"))
      (node (ref "U4") (pin "M22") (pinfunction "BIGCPU_VDD_7_M22") (pintype "power_in"))
      (node (ref "U4") (pin "N20") (pinfunction "BIGCPU_VDD_10_N20") (pintype "power_in"))
      (node (ref "U4") (pin "N22") (pinfunction "BIGCPU_VDD_9_N22") (pintype "power_in"))
    )
    (net (code "6") (name "VDD_CPU_L") (class "Default")
      (node (ref "C110") (pin "2") (pinfunction "2_2") (pintype "passive"))
      (node (ref "C113") (pin "2") (pinfunction "2_2") (pintype "passive"))
      (node (ref "C117") (pin "2") (pinfunction "2_2") (pintype "passive"))
      (node (ref "C72") (pin "2") (pinfunction "2_2") (pintype "passive"))
      (node (ref "C95") (pin "2") (pinfunction "2_2") (pintype "passive"))
      (node (ref "U4") (pin "P20") (pinfunction "LITCPU_VDD_1_P20") (pintype "power_in"))
      (node (ref "U4") (pin "P22") (pinfunction "LITCPU_VDD_4_P22") (pintype "power_in"))
      (node (ref "U4") (pin "R19") (pinfunction "LITCPU_VDD_2_R19") (pintype "power_in"))
      (node (ref "U4") (pin "R20") (pinfunction "LITCPU_VDD_3_R20") (pintype "power_in"))
      (node (ref "U4") (pin "R22") (pinfunction "LITCPU_VDD_7_R22") (pintype "power_in"))
      (node (ref "U4") (pin "T20") (pinfunction "LITCPU_VDD_6_T20") (pintype "power_in"))
      (node (ref "U4") (pin "T22") (pinfunction "LITCPU_VDD_5_T22") (pintype "power_in"))
    )
    (net (code "7") (name "VDD_GPU") (class "Default")
      (node (ref "C100") (pin "2") (pinfunction "2_2") (pintype "passive"))
      (node (ref "C102") (pin "2") (pinfunction "2_2") (pintype "passive"))
      (node (ref "C103") (pin "2") (pinfunction "2_2") (pintype "passive"))
      (node (ref "C105") (pin "2") (pinfunction "2_2") (pintype "passive"))
      (node (ref "C106") (pin "2") (pinfunction "2_2") (pintype "passive"))
      (node (ref "C107") (pin "2") (pinfunction "2_2") (pintype "passive"))
      (node (ref "C108") (pin "2") (pinfunction "2_2") (pintype "passive"))
      (node (ref "C109") (pin "2") (pinfunction "2_2") (pintype "passive"))
      (node (ref "C111") (pin "2") (pinfunction "2_2") (pintype "passive"))
      (node (ref "C92") (pin "2") (pinfunction "2_2") (pintype "passive"))
      (node (ref "U4") (pin "R11") (pinfunction "GPU_VDD_8_R11") (pintype "power_in"))
      (node (ref "U4") (pin "R12") (pinfunction "GPU_VDD_9_R12") (pintype "power_in"))
      (node (ref "U4") (pin "R13") (pinfunction "GPU_VDD_13_R13") (pintype "power_in"))
      (node (ref "U4") (pin "T11") (pinfunction "GPU_VDD_10_T11") (pintype "power_in"))
      (node (ref "U4") (pin "T12") (pinfunction "GPU_VDD_11_T12") (pintype "power_in"))
      (node (ref "U4") (pin "T13") (pinfunction "GPU_VDD_12_T13") (pintype "power_in"))
      (node (ref "U4") (pin "T14") (pinfunction "GPU_VDD_14_T14") (pintype "power_in"))
      (node (ref "U4") (pin "U13") (pinfunction "GPU_VDD_7_U13") (pintype "power_in"))
      (node (ref "U4") (pin "V11") (pinfunction "GPU_VDD_15_V11") (pintype "power_in"))
      (node (ref "U4") (pin "V12") (pinfunction "GPU_VDD_16_V12") (pintype "power_in"))
      (node (ref "U4") (pin "V13") (pinfunction "GPU_VDD_6_V13") (pintype "power_in"))
      (node (ref "U4") (pin "V14") (pinfunction "GPU_VDD_5_V14") (pintype "power_in"))
      (node (ref "U4") (pin "V15") (pinfunction "GPU_VDD_4_V15") (pintype "power_in"))
      (node (ref "U4") (pin "V16") (pinfunction "GPU_VDD_17_V16") (pintype "power_in"))
      (node (ref "U4") (pin "W10") (pinfunction "GPU_VDD_20_W10") (pintype "power_in"))
      (node (ref "U4") (pin "W11") (pinfunction "GPU_VDD_1_W11") (pintype "power_in"))
      (node (ref "U4") (pin "W12") (pinfunction "GPU_VDD_2_W12") (pintype "power_in"))
      (node (ref "U4") (pin "W14") (pinfunction "GPU_VDD_3_W14") (pintype "power_in"))
      (node (ref "U4") (pin "W15") (pinfunction "GPU_VDD_19_W15") (pintype "power_in"))
      (node (ref "U4") (pin "W16") (pinfunction "GPU_VDD_18_W16") (pintype "power_in"))
    )
    (net (code "8") (name "VDD_LOG") (class "Default")
      (node (ref "C101") (pin "2") (pinfunction "2_2") (pintype "passive"))
      (node (ref "C94") (pin "2") (pinfunction "2_2") (pintype "passive"))
      (node (ref "C96") (pin "2") (pinfunction "2_2") (pintype "passive"))
      (node (ref "C97") (pin "2") (pinfunction "2_2") (pintype "passive"))
      (node (ref "C98") (pin "2") (pinfunction "2_2") (pintype "passive"))
      (node (ref "C99") (pin "2") (pinfunction "2_2") (pintype "passive"))
      (node (ref "U4") (pin "L17") (pinfunction "LOGIC_VDD_10_L17") (pintype "power_in"))
      (node (ref "U4") (pin "M17") (pinfunction "LOGIC_VDD_9_M17") (pintype "power_in"))
      (node (ref "U4") (pin "T17") (pinfunction "LOGIC_VDD_11_T17") (pintype "power_in"))
      (node (ref "U4") (pin "U17") (pinfunction "LOGIC_VDD_8_U17") (pintype "power_in"))
      (node (ref "U4") (pin "U18") (pinfunction "LOGIC_VDD_7_U18") (pintype "power_in"))
      (node (ref "U4") (pin "U20") (pinfunction "LOGIC_VDD_12_U20") (pintype "power_in"))
      (node (ref "U4") (pin "V18") (pinfunction "LOGIC_VDD_5_V18") (pintype "power_in"))
      (node (ref "U4") (pin "V19") (pinfunction "LOGIC_VDD_4_V19") (pintype "power_in"))
      (node (ref "U4") (pin "V20") (pinfunction "LOGIC_VDD_3_V20") (pintype "power_in"))
      (node (ref "U4") (pin "V21") (pinfunction "LOGIC_VDD_2_V21") (pintype "power_in"))
      (node (ref "U4") (pin "V22") (pinfunction "LOGIC_VDD_1_V22") (pintype "power_in"))
      (node (ref "U4") (pin "W20") (pinfunction "LOGIC_VDD_6_W20") (pintype "power_in"))
    )
  )
)
